# MW-Mega-Shield.net
KiCad netlist of a schematic drawn in EAGLE
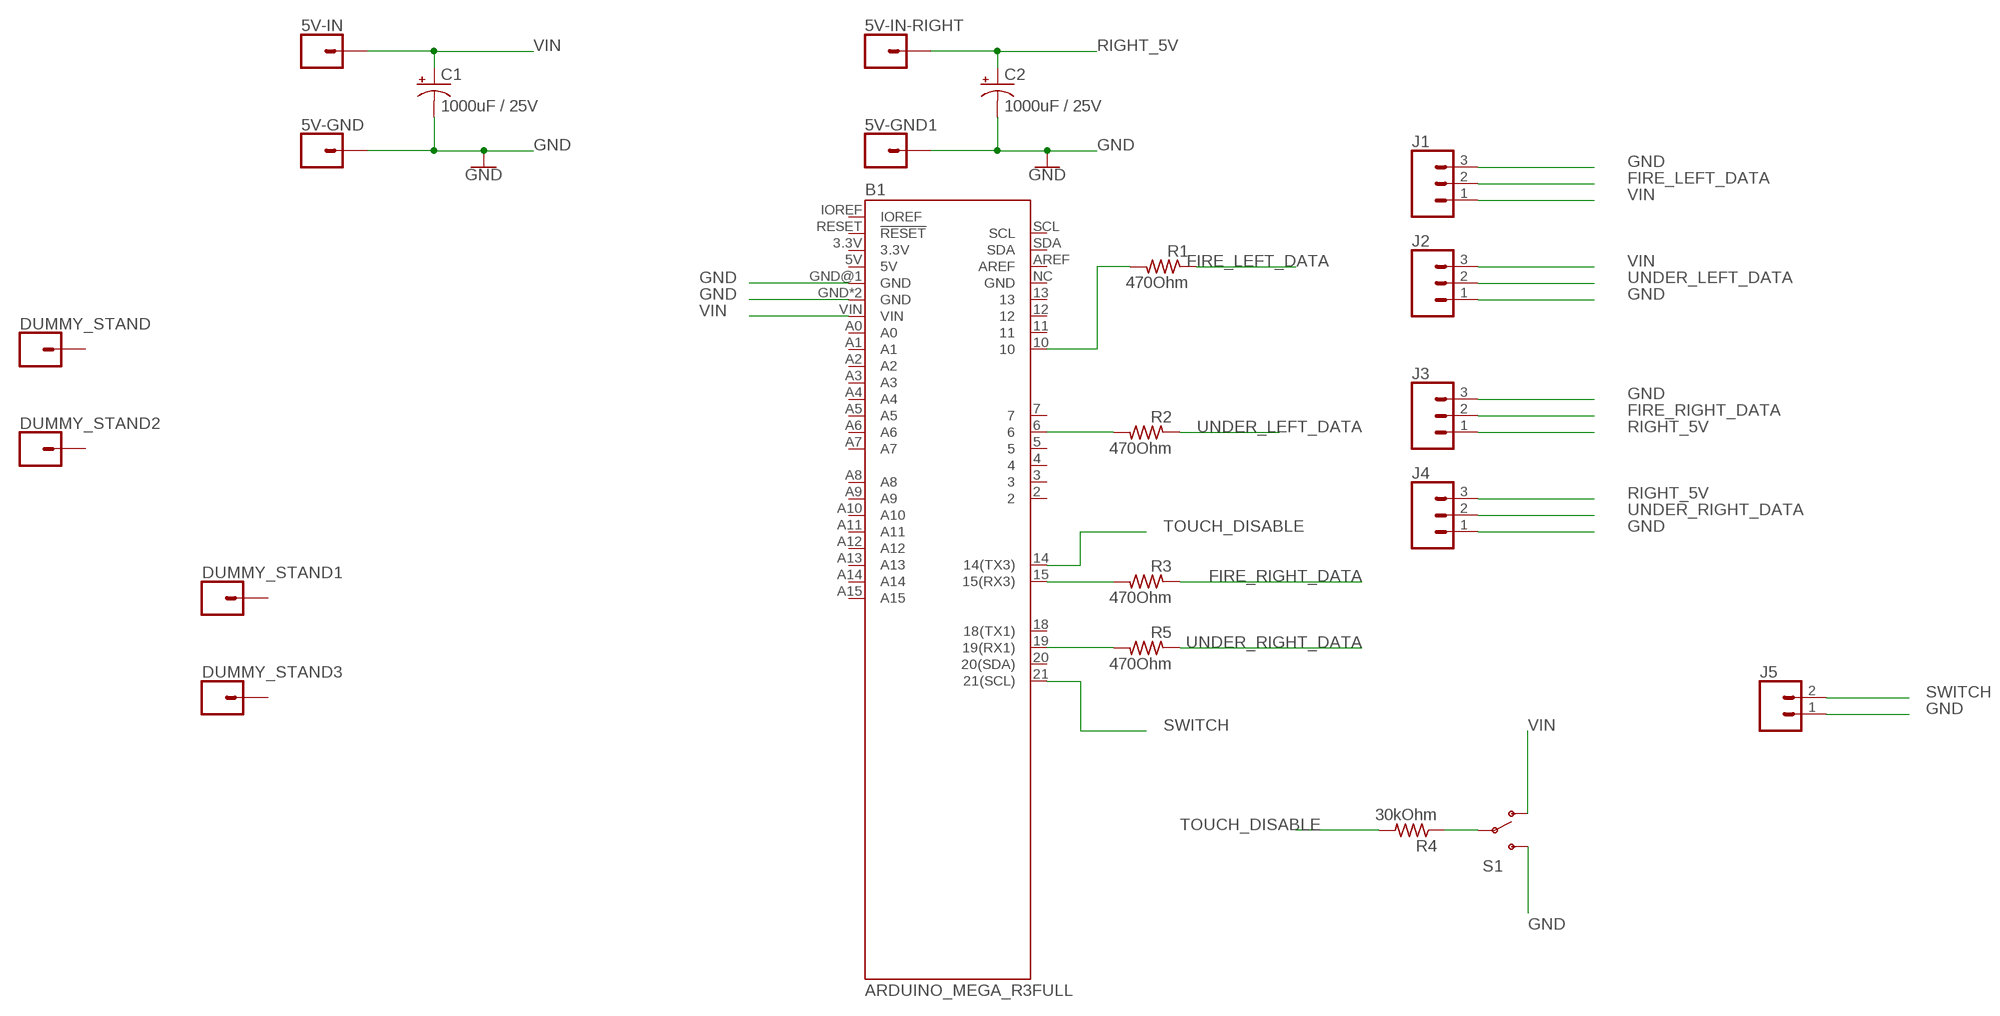
[diagram p0: schematic, sheet 1]

(export (version "E")
  (design (tool "Eeschema 10.0.6"))
  (components
    (comp (ref "5V-GND")
      (value "CONN_01")
      (footprint "eagle-import:1X01")
      (libsource (lib "eagle-import") (part "CONN_01"))
    )
    (comp (ref "5V-GND1")
      (value "CONN_01")
      (footprint "eagle-import:1X01")
      (libsource (lib "eagle-import") (part "CONN_01"))
    )
    (comp (ref "5V-IN")
      (value "CONN_01")
      (footprint "eagle-import:1X01")
      (libsource (lib "eagle-import") (part "CONN_01"))
    )
    (comp (ref "5V-IN-RIGHT")
      (value "CONN_01")
      (footprint "eagle-import:1X01")
      (libsource (lib "eagle-import") (part "CONN_01"))
    )
    (comp (ref "B1")
      (value "ARDUINO_MEGA_R3FULL")
      (footprint "eagle-import:ARDUINO_MEGA_NO_SILK")
      (libsource (lib "eagle-import") (part "ARDUINO_MEGA_R3FULL"))
    )
    (comp (ref "C1")
      (value "1000uF / 25V")
      (footprint "eagle-import:E5-10,5")
      (libsource (lib "eagle-import") (part "CPOL-USE5-10.5"))
    )
    (comp (ref "C2")
      (value "1000uF / 25V")
      (footprint "eagle-import:E5-10,5")
      (libsource (lib "eagle-import") (part "CPOL-USE5-10.5"))
    )
    (comp (ref "DUMMY_STAND")
      (value "CONN_01")
      (footprint "eagle-import:1X01")
      (libsource (lib "eagle-import") (part "CONN_01"))
    )
    (comp (ref "DUMMY_STAND1")
      (value "CONN_01")
      (footprint "eagle-import:1X01")
      (libsource (lib "eagle-import") (part "CONN_01"))
    )
    (comp (ref "DUMMY_STAND2")
      (value "CONN_01")
      (footprint "eagle-import:1X01")
      (libsource (lib "eagle-import") (part "CONN_01"))
    )
    (comp (ref "DUMMY_STAND3")
      (value "CONN_01")
      (footprint "eagle-import:1X01")
      (libsource (lib "eagle-import") (part "CONN_01"))
    )
    (comp (ref "J1")
      (value "CONN_03SCREW-NS")
      (footprint "eagle-import:SCREWTERMINAL-3.5MM-3-NS")
      (libsource (lib "eagle-import") (part "CONN_03SCREW-NS"))
    )
    (comp (ref "J2")
      (value "CONN_03SCREW-NS")
      (footprint "eagle-import:SCREWTERMINAL-3.5MM-3-NS")
      (libsource (lib "eagle-import") (part "CONN_03SCREW-NS"))
    )
    (comp (ref "J3")
      (value "CONN_03SCREW-NS")
      (footprint "eagle-import:SCREWTERMINAL-3.5MM-3-NS")
      (libsource (lib "eagle-import") (part "CONN_03SCREW-NS"))
    )
    (comp (ref "J4")
      (value "CONN_03SCREW-NS")
      (footprint "eagle-import:SCREWTERMINAL-3.5MM-3-NS")
      (libsource (lib "eagle-import") (part "CONN_03SCREW-NS"))
    )
    (comp (ref "J5")
      (value "CONN_02")
      (footprint "eagle-import:1X02")
      (libsource (lib "eagle-import") (part "CONN_02"))
    )
    (comp (ref "R1")
      (value "470Ohm")
      (footprint "eagle-import:R0603")
      (libsource (lib "eagle-import") (part "R-US_R0603"))
    )
    (comp (ref "R2")
      (value "470Ohm")
      (footprint "eagle-import:R0603")
      (libsource (lib "eagle-import") (part "R-US_R0603"))
    )
    (comp (ref "R3")
      (value "470Ohm")
      (footprint "eagle-import:R0603")
      (libsource (lib "eagle-import") (part "R-US_R0603"))
    )
    (comp (ref "R4")
      (value "30kOhm")
      (footprint "eagle-import:R0603")
      (libsource (lib "eagle-import") (part "R-US_R0603"))
    )
    (comp (ref "R5")
      (value "470Ohm")
      (footprint "eagle-import:R0603")
      (libsource (lib "eagle-import") (part "R-US_R0603"))
    )
    (comp (ref "S1")
      (value "SWITCH-SPDTSMD")
      (footprint "eagle-import:SWITCH_SPDT_SMD")
      (libsource (lib "eagle-import") (part "SWITCH-SPDTSMD"))
    )
  )
  (nets
    (net (code "1") (name "/FIRE_LEFT_DATA") (class "Default")
      (node (ref "J1") (pin "2") (pinfunction "2_2") (pintype "passive"))
      (node (ref "R1") (pin "1") (pinfunction "1_1") (pintype "passive"))
    )
    (net (code "2") (name "/FIRE_RIGHT_DATA") (class "Default")
      (node (ref "J3") (pin "2") (pinfunction "2_2") (pintype "passive"))
      (node (ref "R3") (pin "1") (pinfunction "1_1") (pintype "passive"))
    )
    (net (code "3") (name "/RIGHT_5V") (class "Default")
      (node (ref "5V-IN-RIGHT") (pin "1") (pinfunction "1_1") (pintype "passive"))
      (node (ref "C2") (pin "+") (pinfunction "+_+") (pintype "passive"))
      (node (ref "J3") (pin "1") (pinfunction "1_1") (pintype "passive"))
      (node (ref "J4") (pin "3") (pinfunction "3_3") (pintype "passive"))
    )
    (net (code "4") (name "/SWITCH") (class "Default")
      (node (ref "B1") (pin "21") (pinfunction "21(SCL)_21") (pintype "bidirectional"))
      (node (ref "J5") (pin "2") (pinfunction "2_2") (pintype "passive"))
    )
    (net (code "5") (name "/TOUCH_DISABLE") (class "Default")
      (node (ref "B1") (pin "14") (pinfunction "14(TX3)_14") (pintype "bidirectional"))
      (node (ref "R4") (pin "2") (pinfunction "2_2") (pintype "passive"))
    )
    (net (code "6") (name "/UNDER_LEFT_DATA") (class "Default")
      (node (ref "J2") (pin "2") (pinfunction "2_2") (pintype "passive"))
      (node (ref "R2") (pin "1") (pinfunction "1_1") (pintype "passive"))
    )
    (net (code "7") (name "/UNDER_RIGHT_DATA") (class "Default")
      (node (ref "J4") (pin "2") (pinfunction "2_2") (pintype "passive"))
      (node (ref "R5") (pin "1") (pinfunction "1_1") (pintype "passive"))
    )
    (net (code "8") (name "/VIN") (class "Default")
      (node (ref "5V-IN") (pin "1") (pinfunction "1_1") (pintype "passive"))
      (node (ref "B1") (pin "VIN") (pinfunction "VIN_VIN") (pintype "bidirectional"))
      (node (ref "C1") (pin "+") (pinfunction "+_+") (pintype "passive"))
      (node (ref "J1") (pin "1") (pinfunction "1_1") (pintype "passive"))
      (node (ref "J2") (pin "3") (pinfunction "3_3") (pintype "passive"))
      (node (ref "S1") (pin "1") (pinfunction "O_1") (pintype "passive"))
    )
    (net (code "9") (name "GND") (class "Default")
      (node (ref "5V-GND") (pin "1") (pinfunction "1_1") (pintype "passive"))
      (node (ref "5V-GND1") (pin "1") (pinfunction "1_1") (pintype "passive"))
      (node (ref "B1") (pin "GND") (pinfunction "GND_GND") (pintype "bidirectional"))
      (node (ref "B1") (pin "GND@1") (pinfunction "GND_GND@1") (pintype "bidirectional"))
      (node (ref "B1") (pin "GND@4") (pinfunction "GND_GND@4") (pintype "bidirectional"))
      (node (ref "C1") (pin "-") (pinfunction "-_-") (pintype "passive"))
      (node (ref "C2") (pin "-") (pinfunction "-_-") (pintype "passive"))
      (node (ref "J1") (pin "3") (pinfunction "3_3") (pintype "passive"))
      (node (ref "J2") (pin "1") (pinfunction "1_1") (pintype "passive"))
      (node (ref "J3") (pin "3") (pinfunction "3_3") (pintype "passive"))
      (node (ref "J4") (pin "1") (pinfunction "1_1") (pintype "passive"))
      (node (ref "J5") (pin "1") (pinfunction "1_1") (pintype "passive"))
      (node (ref "S1") (pin "3") (pinfunction "S_3") (pintype "passive"))
    )
    (net (code "10") (name "Net-(B1-15(RX3))") (class "Default")
      (node (ref "B1") (pin "15") (pinfunction "15(RX3)_15") (pintype "bidirectional"))
      (node (ref "R3") (pin "2") (pinfunction "2_2") (pintype "passive"))
    )
    (net (code "11") (name "Net-(B1-19(RX1))") (class "Default")
      (node (ref "B1") (pin "19") (pinfunction "19(RX1)_19") (pintype "bidirectional"))
      (node (ref "R5") (pin "2") (pinfunction "2_2") (pintype "passive"))
    )
    (net (code "12") (name "Net-(B1-Pad6)") (class "Default")
      (node (ref "B1") (pin "6") (pinfunction "6_6") (pintype "bidirectional"))
      (node (ref "R2") (pin "2") (pinfunction "2_2") (pintype "passive"))
    )
    (net (code "13") (name "Net-(B1-Pad10)") (class "Default")
      (node (ref "B1") (pin "10") (pinfunction "10_10") (pintype "bidirectional"))
      (node (ref "R1") (pin "2") (pinfunction "2_2") (pintype "passive"))
    )
    (net (code "14") (name "Net-(S1-P)") (class "Default")
      (node (ref "R4") (pin "1") (pinfunction "1_1") (pintype "passive"))
      (node (ref "S1") (pin "2") (pinfunction "P_2") (pintype "passive"))
    )
    (net (code "15") (name "unconnected-(B1-18(TX1)-Pad18)") (class "Default")
      (node (ref "B1") (pin "18") (pinfunction "18(TX1)_18") (pintype "bidirectional"))
    )
    (net (code "16") (name "unconnected-(B1-20(SDA)-Pad20)") (class "Default")
      (node (ref "B1") (pin "20") (pinfunction "20(SDA)_20") (pintype "bidirectional"))
    )
    (net (code "17") (name "unconnected-(B1-GND-PadNC)") (class "Default")
      (node (ref "B1") (pin "NC") (pinfunction "GND_NC") (pintype "bidirectional"))
    )
    (net (code "18") (name "unconnected-(B1-Pad2)") (class "Default")
      (node (ref "B1") (pin "2") (pinfunction "2_2") (pintype "bidirectional"))
    )
    (net (code "19") (name "unconnected-(B1-Pad3)") (class "Default")
      (node (ref "B1") (pin "3") (pinfunction "3_3") (pintype "bidirectional"))
    )
    (net (code "20") (name "unconnected-(B1-Pad3.3V)") (class "Default")
      (node (ref "B1") (pin "3.3V") (pinfunction "3.3V_3.3V") (pintype "bidirectional"))
    )
    (net (code "21") (name "unconnected-(B1-Pad4)") (class "Default")
      (node (ref "B1") (pin "4") (pinfunction "4_4") (pintype "bidirectional"))
    )
    (net (code "22") (name "unconnected-(B1-Pad5)") (class "Default")
      (node (ref "B1") (pin "5") (pinfunction "5_5") (pintype "bidirectional"))
    )
    (net (code "23") (name "unconnected-(B1-Pad5V)") (class "Default")
      (node (ref "B1") (pin "5V") (pinfunction "5V_5V") (pintype "bidirectional"))
    )
    (net (code "24") (name "unconnected-(B1-Pad7)") (class "Default")
      (node (ref "B1") (pin "7") (pinfunction "7_7") (pintype "bidirectional"))
    )
    (net (code "25") (name "unconnected-(B1-Pad11)") (class "Default")
      (node (ref "B1") (pin "11") (pinfunction "11_11") (pintype "bidirectional"))
    )
    (net (code "26") (name "unconnected-(B1-Pad12)") (class "Default")
      (node (ref "B1") (pin "12") (pinfunction "12_12") (pintype "bidirectional"))
    )
    (net (code "27") (name "unconnected-(B1-Pad13)") (class "Default")
      (node (ref "B1") (pin "13") (pinfunction "13_13") (pintype "bidirectional"))
    )
    (net (code "28") (name "unconnected-(B1-PadA0)") (class "Default")
      (node (ref "B1") (pin "A0") (pinfunction "A0_A0") (pintype "bidirectional"))
    )
    (net (code "29") (name "unconnected-(B1-PadA1)") (class "Default")
      (node (ref "B1") (pin "A1") (pinfunction "A1_A1") (pintype "bidirectional"))
    )
    (net (code "30") (name "unconnected-(B1-PadA2)") (class "Default")
      (node (ref "B1") (pin "A2") (pinfunction "A2_A2") (pintype "bidirectional"))
    )
    (net (code "31") (name "unconnected-(B1-PadA3)") (class "Default")
      (node (ref "B1") (pin "A3") (pinfunction "A3_A3") (pintype "bidirectional"))
    )
    (net (code "32") (name "unconnected-(B1-PadA4)") (class "Default")
      (node (ref "B1") (pin "A4") (pinfunction "A4_A4") (pintype "bidirectional"))
    )
    (net (code "33") (name "unconnected-(B1-PadA5)") (class "Default")
      (node (ref "B1") (pin "A5") (pinfunction "A5_A5") (pintype "bidirectional"))
    )
    (net (code "34") (name "unconnected-(B1-PadA6)") (class "Default")
      (node (ref "B1") (pin "A6") (pinfunction "A6_A6") (pintype "bidirectional"))
    )
    (net (code "35") (name "unconnected-(B1-PadA7)") (class "Default")
      (node (ref "B1") (pin "A7") (pinfunction "A7_A7") (pintype "bidirectional"))
    )
    (net (code "36") (name "unconnected-(B1-PadA8)") (class "Default")
      (node (ref "B1") (pin "A8") (pinfunction "A8_A8") (pintype "bidirectional"))
    )
    (net (code "37") (name "unconnected-(B1-PadA9)") (class "Default")
      (node (ref "B1") (pin "A9") (pinfunction "A9_A9") (pintype "bidirectional"))
    )
    (net (code "38") (name "unconnected-(B1-PadA10)") (class "Default")
      (node (ref "B1") (pin "A10") (pinfunction "A10_A10") (pintype "bidirectional"))
    )
    (net (code "39") (name "unconnected-(B1-PadA11)") (class "Default")
      (node (ref "B1") (pin "A11") (pinfunction "A11_A11") (pintype "bidirectional"))
    )
    (net (code "40") (name "unconnected-(B1-PadA12)") (class "Default")
      (node (ref "B1") (pin "A12") (pinfunction "A12_A12") (pintype "bidirectional"))
    )
    (net (code "41") (name "unconnected-(B1-PadA13)") (class "Default")
      (node (ref "B1") (pin "A13") (pinfunction "A13_A13") (pintype "bidirectional"))
    )
    (net (code "42") (name "unconnected-(B1-PadA14)") (class "Default")
      (node (ref "B1") (pin "A14") (pinfunction "A14_A14") (pintype "bidirectional"))
    )
    (net (code "43") (name "unconnected-(B1-PadA15)") (class "Default")
      (node (ref "B1") (pin "A15") (pinfunction "A15_A15") (pintype "bidirectional"))
    )
    (net (code "44") (name "unconnected-(B1-PadAREF)") (class "Default")
      (node (ref "B1") (pin "AREF") (pinfunction "AREF_AREF") (pintype "bidirectional"))
    )
    (net (code "45") (name "unconnected-(B1-PadIOREF)") (class "Default")
      (node (ref "B1") (pin "IOREF") (pinfunction "IOREF_IOREF") (pintype "bidirectional"))
    )
    (net (code "46") (name "unconnected-(B1-PadSCL)") (class "Default")
      (node (ref "B1") (pin "SCL") (pinfunction "SCL_SCL") (pintype "bidirectional"))
    )
    (net (code "47") (name "unconnected-(B1-PadSDA)") (class "Default")
      (node (ref "B1") (pin "SDA") (pinfunction "SDA_SDA") (pintype "bidirectional"))
    )
    (net (code "48") (name "unconnected-(B1-~{RESET}-PadRESET)") (class "Default")
      (node (ref "B1") (pin "RESET") (pinfunction "~{RESET}_RESET") (pintype "bidirectional"))
    )
    (net (code "49") (name "unconnected-(DUMMY_STAND-Pad1)") (class "Default")
      (node (ref "DUMMY_STAND") (pin "1") (pinfunction "1_1") (pintype "passive"))
    )
    (net (code "50") (name "unconnected-(DUMMY_STAND1-Pad1)") (class "Default")
      (node (ref "DUMMY_STAND1") (pin "1") (pinfunction "1_1") (pintype "passive"))
    )
    (net (code "51") (name "unconnected-(DUMMY_STAND2-Pad1)") (class "Default")
      (node (ref "DUMMY_STAND2") (pin "1") (pinfunction "1_1") (pintype "passive"))
    )
    (net (code "52") (name "unconnected-(DUMMY_STAND3-Pad1)") (class "Default")
      (node (ref "DUMMY_STAND3") (pin "1") (pinfunction "1_1") (pintype "passive"))
    )
  )
)
